# adns3050_v7.net
KiCad netlist of a schematic drawn in EAGLE
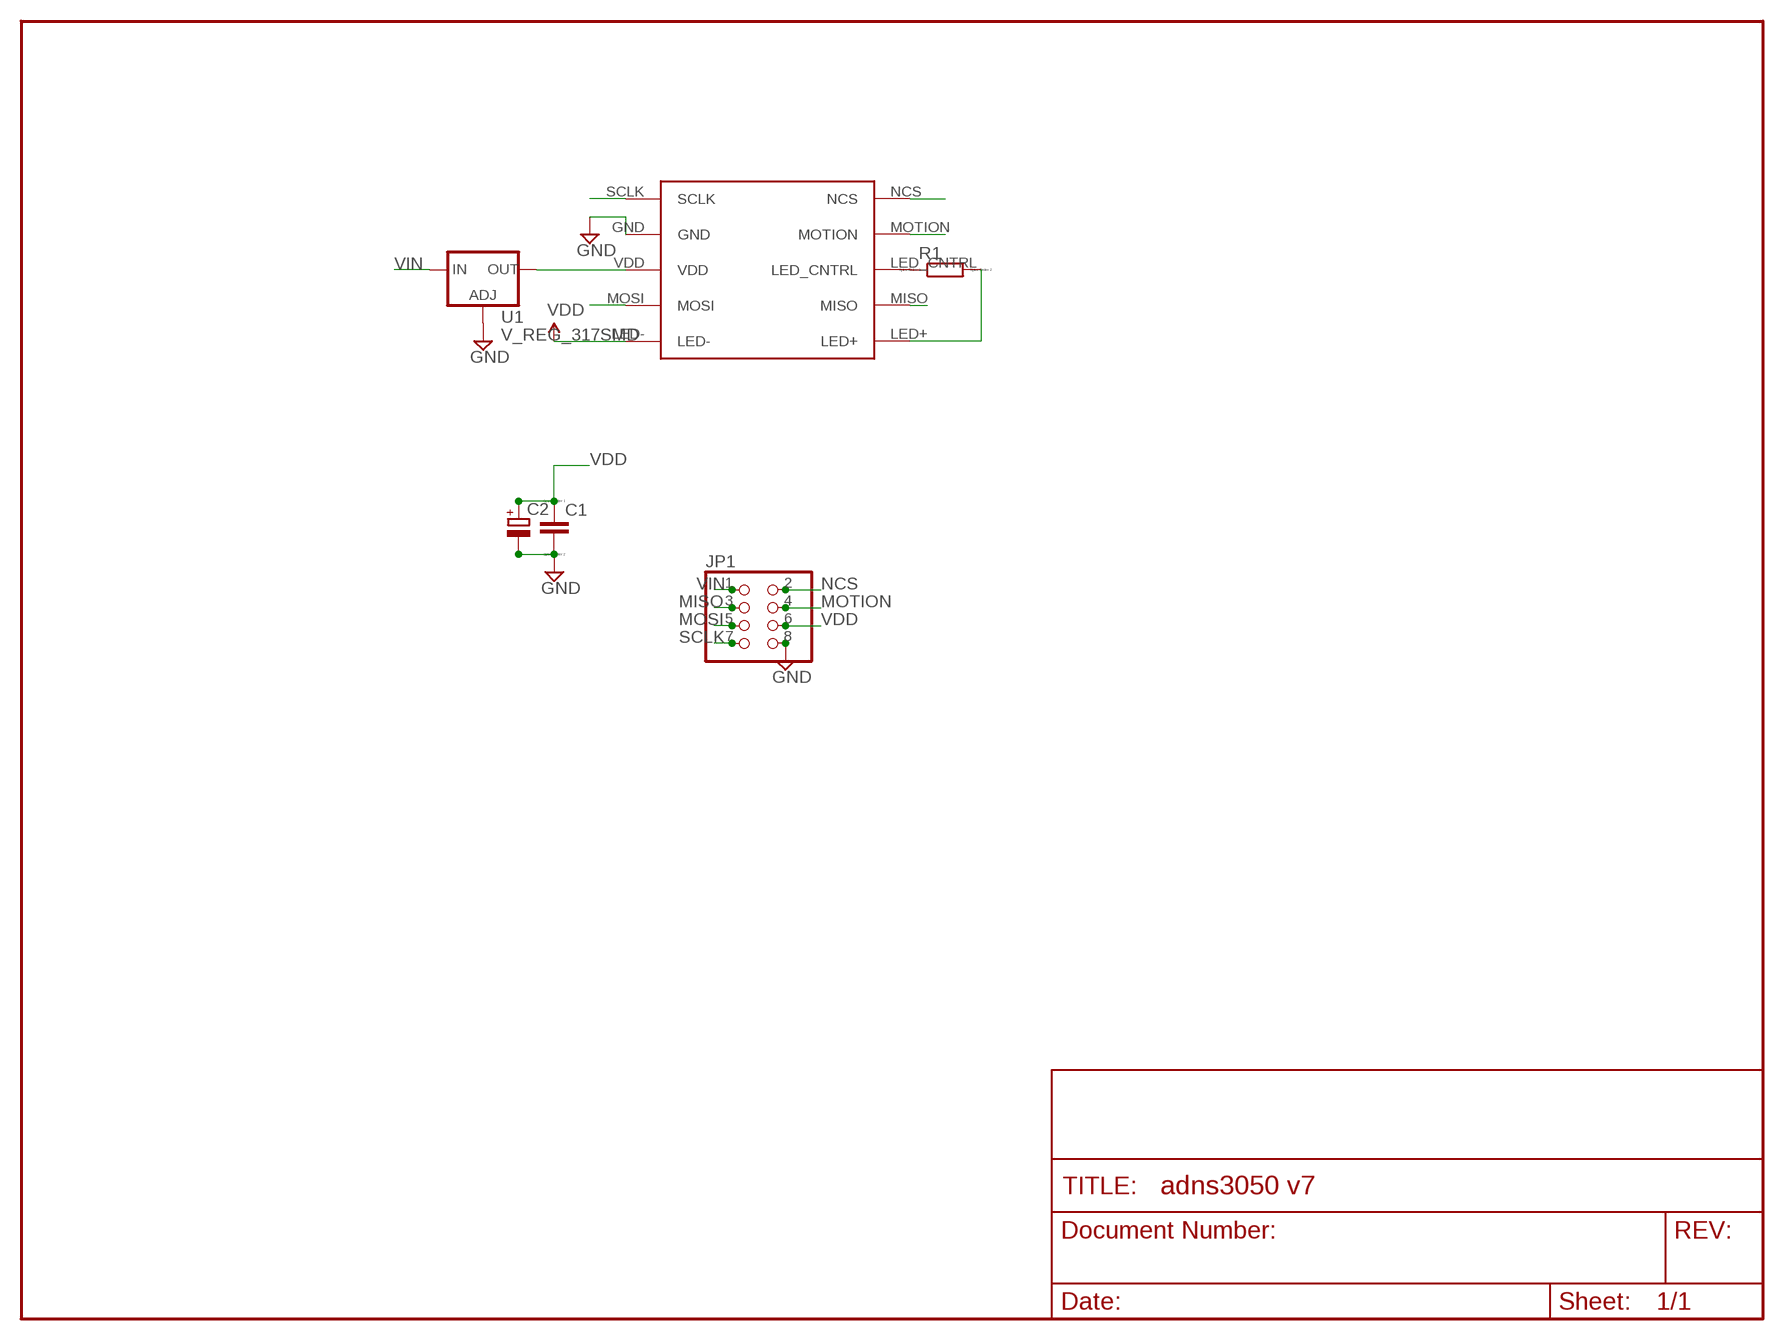
[diagram p0: schematic, sheet 1]

(export (version "E")
  (design (tool "Eeschema 10.0.6"))
  (components
    (comp (ref "C1")
      (value "CC0603")
      (footprint "eagle-import:C0603")
      (libsource (lib "eagle-import") (part "CC0603"))
    )
    (comp (ref "C2")
      (value "CPOL-EUR/2012-12R")
      (footprint "eagle-import:R_2012-12R")
      (libsource (lib "eagle-import") (part "CPOL-EUR/2012-12R"))
    )
    (comp (ref "JP1")
      (value "PINHD-2X4")
      (footprint "eagle-import:2X04")
      (libsource (lib "eagle-import") (part "PINHD-2X4"))
    )
    (comp (ref "R1")
      (value "RR0603")
      (footprint "eagle-import:R0603")
      (libsource (lib "eagle-import") (part "RR0603"))
    )
    (comp (ref "U$1")
      (value "3050")
      (footprint "eagle-import:ADNS3")
      (libsource (lib "eagle-import") (part "3050"))
    )
    (comp (ref "U1")
      (value "V_REG_317SMD")
      (footprint "eagle-import:SOT223")
      (libsource (lib "eagle-import") (part "V_REG_317SMD"))
    )
  )
  (nets
    (net (code "1") (name "/MISO") (class "Default")
      (node (ref "JP1") (pin "3") (pinfunction "3_3") (pintype "passive"))
      (node (ref "U$1") (pin "MISO") (pinfunction "MISO_MISO") (pintype "bidirectional"))
    )
    (net (code "2") (name "/MOSI") (class "Default")
      (node (ref "JP1") (pin "5") (pinfunction "5_5") (pintype "passive"))
      (node (ref "U$1") (pin "MOSI") (pinfunction "MOSI_MOSI") (pintype "bidirectional"))
    )
    (net (code "3") (name "/MOTION") (class "Default")
      (node (ref "JP1") (pin "4") (pinfunction "4_4") (pintype "passive"))
      (node (ref "U$1") (pin "MOTION") (pinfunction "MOTION_MOTION") (pintype "bidirectional"))
    )
    (net (code "4") (name "/NCS") (class "Default")
      (node (ref "JP1") (pin "2") (pinfunction "2_2") (pintype "passive"))
      (node (ref "U$1") (pin "NCS") (pinfunction "NCS_NCS") (pintype "bidirectional"))
    )
    (net (code "5") (name "/SCLK") (class "Default")
      (node (ref "JP1") (pin "7") (pinfunction "7_7") (pintype "passive"))
      (node (ref "U$1") (pin "SCLK") (pinfunction "SCLK_SCLK") (pintype "bidirectional"))
    )
    (net (code "6") (name "/VIN") (class "Default")
      (node (ref "JP1") (pin "1") (pinfunction "1_1") (pintype "passive"))
      (node (ref "U1") (pin "3") (pinfunction "IN_3") (pintype "input"))
    )
    (net (code "7") (name "GND") (class "Default")
      (node (ref "C1") (pin "2") (pinfunction "2_2") (pintype "passive"))
      (node (ref "C2") (pin "-") (pinfunction "-_-") (pintype "passive"))
      (node (ref "JP1") (pin "8") (pinfunction "8_8") (pintype "passive"))
      (node (ref "U$1") (pin "GND") (pinfunction "GND_GND") (pintype "bidirectional"))
      (node (ref "U1") (pin "1") (pinfunction "ADJ_1") (pintype "input"))
    )
    (net (code "8") (name "Net-(R1-Pad1)") (class "Default")
      (node (ref "R1") (pin "1") (pinfunction "1_1") (pintype "passive"))
      (node (ref "U$1") (pin "LED_CNTRL") (pinfunction "LED_CNTRL_LED_CNTRL") (pintype "bidirectional"))
    )
    (net (code "9") (name "Net-(R1-Pad2)") (class "Default")
      (node (ref "R1") (pin "2") (pinfunction "2_2") (pintype "passive"))
      (node (ref "U$1") (pin "LED+") (pinfunction "LED+_LED+") (pintype "bidirectional"))
    )
    (net (code "10") (name "VDD") (class "Default")
      (node (ref "C1") (pin "1") (pinfunction "1_1") (pintype "passive"))
      (node (ref "C2") (pin "+") (pinfunction "+_+") (pintype "passive"))
      (node (ref "JP1") (pin "6") (pinfunction "6_6") (pintype "passive"))
      (node (ref "U$1") (pin "LED-") (pinfunction "LED-_LED-") (pintype "bidirectional"))
      (node (ref "U$1") (pin "VDD") (pinfunction "VDD_VDD") (pintype "bidirectional"))
      (node (ref "U1") (pin "2") (pinfunction "OUT_2") (pintype "output"))
    )
  )
)
